# EPM1270.net
KiCad netlist of a schematic drawn in Altium Designer
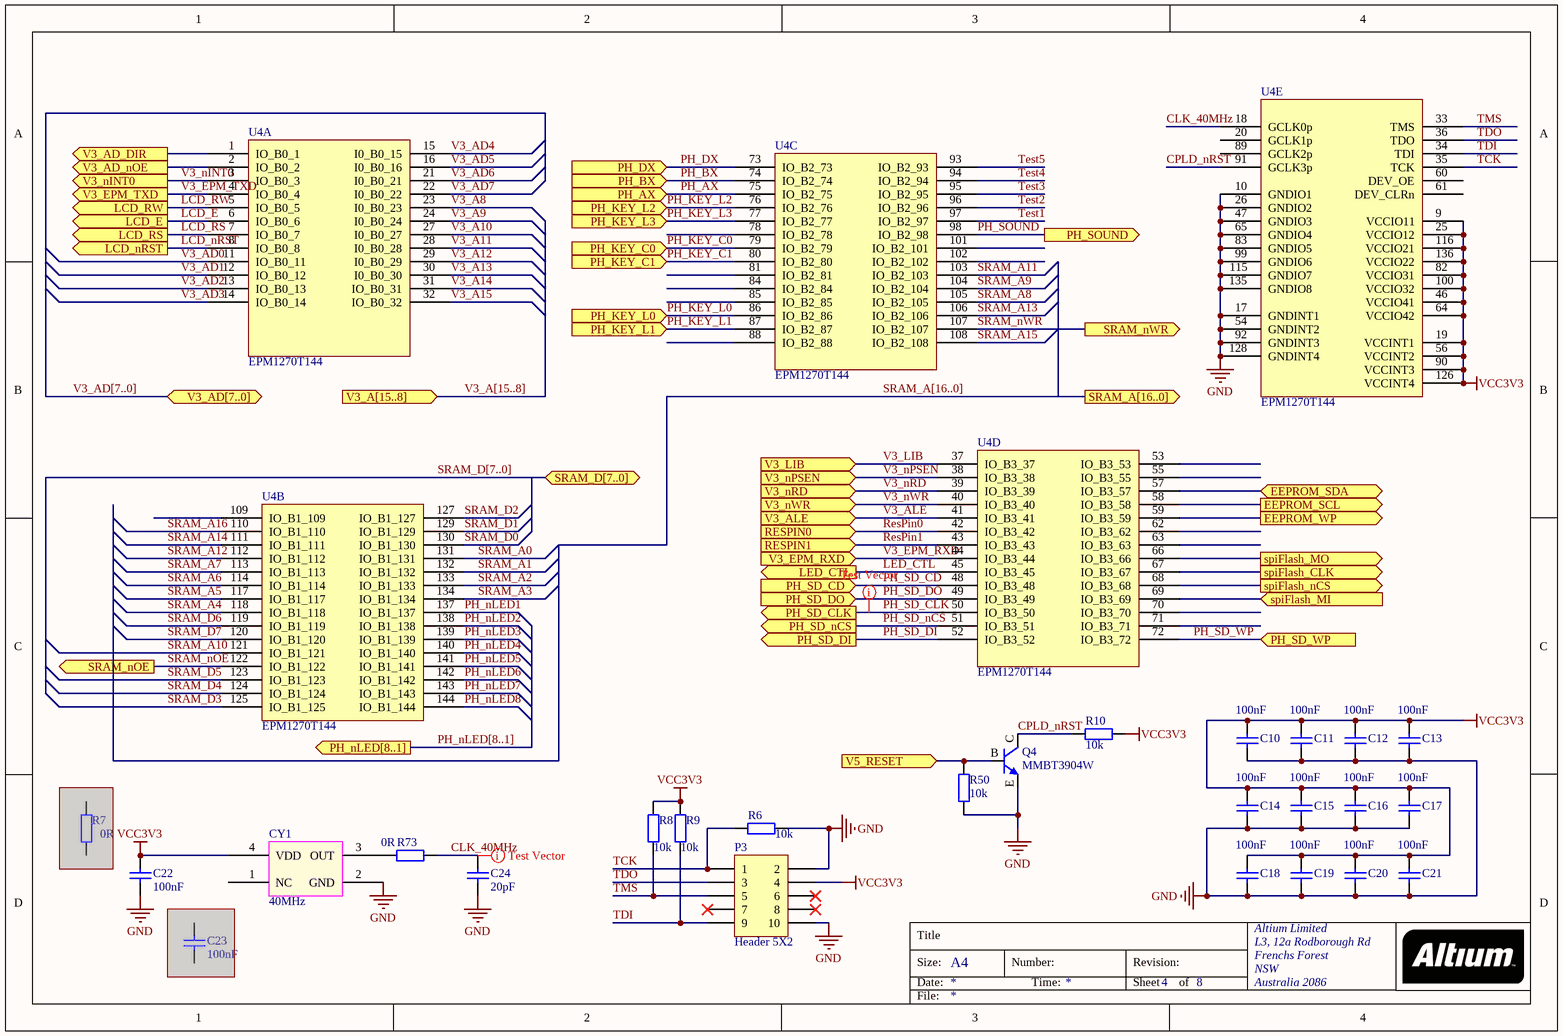
[diagram p0: EPM1270.SchDoc]

(export (version "E")
  (design (tool "Eeschema 10.0.6"))
  (components
    (comp (ref "C10") (value "100nF") (footprint "R0603") (libsource (lib "MyYX") (part "CAP_04")))
    (comp (ref "C11") (value "100nF") (footprint "R0603") (libsource (lib "MyYX") (part "CAP_04")))
    (comp (ref "C12") (value "100nF") (footprint "R0603") (libsource (lib "MyYX") (part "CAP_04")))
    (comp (ref "C13") (value "100nF") (footprint "R0603") (libsource (lib "MyYX") (part "CAP_04")))
    (comp (ref "C14") (value "100nF") (footprint "R0603") (libsource (lib "MyYX") (part "CAP_04")))
    (comp (ref "C15") (value "100nF") (footprint "R0603") (libsource (lib "MyYX") (part "CAP_04")))
    (comp (ref "C16") (value "100nF") (footprint "R0603") (libsource (lib "MyYX") (part "CAP_04")))
    (comp (ref "C17") (value "100nF") (footprint "R0603") (libsource (lib "MyYX") (part "CAP_04")))
    (comp (ref "C18") (value "100nF") (footprint "R0603") (libsource (lib "MyYX") (part "CAP_04")))
    (comp (ref "C19") (value "100nF") (footprint "R0603") (libsource (lib "MyYX") (part "CAP_04")))
    (comp (ref "C20") (value "100nF") (footprint "R0603") (libsource (lib "MyYX") (part "CAP_04")))
    (comp (ref "C21") (value "100nF") (footprint "R0603") (libsource (lib "MyYX") (part "CAP_04")))
    (comp (ref "C22") (value "100nF") (footprint "R0603") (libsource (lib "MyYX") (part "CAP_04")))
    (comp (ref "C23") (value "100nF") (footprint "R0603") (libsource (lib "MyYX") (part "CAP_04")))
    (comp (ref "C24")
      (value "20pF")
      (footprint "R0603")
      (fields (field (name "Comment") "100nF"))
      (libsource (lib "MyYX") (part "CAP_04"))
    )
    (comp (ref "CY1")
      (value "40MHz")
      (footprint "XCY4_5032")
      (description "Active crystal")
      (libsource (lib "MyYX") (part "XTAL_4P"))
    )
    (comp (ref "P3")
      (value "Header 5X2")
      (footprint "HDR2X5")
      (description "Header, 5-Pin, Dual row")
      (fields (field (name "PUBLISHER") "Altium Limited"))
      (libsource (lib "Miscellaneous Connectors") (part "Header 5X2"))
    )
    (comp (ref "Q4") (value "MMBT3904W") (footprint "SOT_23") (libsource (lib "MyYX") (part "MMBT3904TT1G")))
    (comp (ref "R6")
      (value "10k")
      (footprint "R0603")
      (description "0402")
      (libsource (lib "") (part "RES_04_1"))
    )
    (comp (ref "R7")
      (value "0R")
      (footprint "R0603")
      (description "0402")
      (libsource (lib "MyYX") (part "RES_04"))
    )
    (comp (ref "R8")
      (value "10k")
      (footprint "R0603")
      (description "0402")
      (libsource (lib "") (part "RES_04_2"))
    )
    (comp (ref "R9")
      (value "10k")
      (footprint "R0603")
      (description "0402")
      (libsource (lib "") (part "RES_04_2"))
    )
    (comp (ref "R10")
      (value "10k")
      (footprint "R0603")
      (description "0402")
      (libsource (lib "") (part "RES_04_3"))
    )
    (comp (ref "R50")
      (value "10k")
      (footprint "R0603")
      (description "0402")
      (libsource (lib "MyYX") (part "RES_04"))
    )
    (comp (ref "R73")
      (value "0R")
      (footprint "R0603")
      (description "0402")
      (libsource (lib "") (part "RES_04_3"))
    )
    (comp (ref "U4")
      (value "EPM1270T144")
      (footprint "EPM1270T144-TQFP")
      (libsource (lib "MyYX") (part "EPM1270T144"))
    )
  )
  (nets
    (net (code "1") (name "/CLK_40MHz") (class "Default")
      (node (ref "C24") (pin "1") (pinfunction "1_1") (pintype "passive"))
      (node (ref "R73") (pin "2") (pinfunction "2_2") (pintype "passive"))
      (node (ref "U4") (pin "18") (pinfunction "GCLK0p_18") (pintype "passive"))
    )
    (net (code "2") (name "/CPLD_nRST") (class "Default")
      (node (ref "Q4") (pin "C") (pinfunction "C_C") (pintype "passive"))
      (node (ref "R10") (pin "1") (pinfunction "1_1") (pintype "passive"))
      (node (ref "U4") (pin "91") (pinfunction "GCLK3p_91") (pintype "passive"))
    )
    (net (code "3") (name "/EEPROM_SCL") (class "Default")
      (node (ref "U4") (pin "58") (pinfunction "IO_B3_58_58") (pintype "passive"))
    )
    (net (code "4") (name "/EEPROM_SDA") (class "Default")
      (node (ref "U4") (pin "57") (pinfunction "IO_B3_57_57") (pintype "passive"))
    )
    (net (code "5") (name "/EEPROM_WP") (class "Default")
      (node (ref "U4") (pin "59") (pinfunction "IO_B3_59_59") (pintype "passive"))
    )
    (net (code "6") (name "/LCD_E") (class "Default")
      (node (ref "U4") (pin "6") (pinfunction "IO_B0_6_6") (pintype "passive"))
    )
    (net (code "7") (name "/LCD_RS") (class "Default")
      (node (ref "U4") (pin "7") (pinfunction "IO_B0_7_7") (pintype "passive"))
    )
    (net (code "8") (name "/LCD_RW") (class "Default")
      (node (ref "U4") (pin "5") (pinfunction "IO_B0_5_5") (pintype "passive"))
    )
    (net (code "9") (name "/LCD_nRST") (class "Default")
      (node (ref "U4") (pin "8") (pinfunction "IO_B0_8_8") (pintype "passive"))
    )
    (net (code "10") (name "/LED_CTL") (class "Default")
      (node (ref "U4") (pin "45") (pinfunction "IO_B3_45_45") (pintype "passive"))
    )
    (net (code "11") (name "/PH_AX") (class "Default")
      (node (ref "U4") (pin "75") (pinfunction "IO_B2_75_75") (pintype "passive"))
    )
    (net (code "12") (name "/PH_BX") (class "Default")
      (node (ref "U4") (pin "74") (pinfunction "IO_B2_74_74") (pintype "passive"))
    )
    (net (code "13") (name "/PH_DX") (class "Default")
      (node (ref "U4") (pin "73") (pinfunction "IO_B2_73_73") (pintype "passive"))
    )
    (net (code "14") (name "/PH_KEY_C0") (class "Default")
      (node (ref "U4") (pin "79") (pinfunction "IO_B2_79_79") (pintype "passive"))
    )
    (net (code "15") (name "/PH_KEY_C1") (class "Default")
      (node (ref "U4") (pin "80") (pinfunction "IO_B2_80_80") (pintype "passive"))
    )
    (net (code "16") (name "/PH_KEY_L0") (class "Default")
      (node (ref "U4") (pin "86") (pinfunction "IO_B2_86_86") (pintype "passive"))
    )
    (net (code "17") (name "/PH_KEY_L1") (class "Default")
      (node (ref "U4") (pin "87") (pinfunction "IO_B2_87_87") (pintype "passive"))
    )
    (net (code "18") (name "/PH_KEY_L2") (class "Default")
      (node (ref "U4") (pin "76") (pinfunction "IO_B2_76_76") (pintype "passive"))
    )
    (net (code "19") (name "/PH_KEY_L3") (class "Default")
      (node (ref "U4") (pin "77") (pinfunction "IO_B2_77_77") (pintype "passive"))
    )
    (net (code "20") (name "/PH_SD_CD") (class "Default")
      (node (ref "U4") (pin "48") (pinfunction "IO_B3_48_48") (pintype "passive"))
    )
    (net (code "21") (name "/PH_SD_CLK") (class "Default")
      (node (ref "U4") (pin "50") (pinfunction "IO_B3_50_50") (pintype "passive"))
    )
    (net (code "22") (name "/PH_SD_DI") (class "Default")
      (node (ref "U4") (pin "52") (pinfunction "IO_B3_52_52") (pintype "passive"))
    )
    (net (code "23") (name "/PH_SD_DO") (class "Default")
      (node (ref "U4") (pin "49") (pinfunction "IO_B3_49_49") (pintype "passive"))
    )
    (net (code "24") (name "/PH_SD_WP") (class "Default")
      (node (ref "U4") (pin "72") (pinfunction "IO_B3_72_72") (pintype "passive"))
    )
    (net (code "25") (name "/PH_SD_nCS") (class "Default")
      (node (ref "U4") (pin "51") (pinfunction "IO_B3_51_51") (pintype "passive"))
    )
    (net (code "26") (name "/PH_SOUND") (class "Default")
      (node (ref "U4") (pin "98") (pinfunction "IO_B2_98_98") (pintype "passive"))
    )
    (net (code "27") (name "/PH_nLED1") (class "Default")
      (node (ref "U4") (pin "137") (pinfunction "IO_B1_137_137") (pintype "passive"))
    )
    (net (code "28") (name "/PH_nLED2") (class "Default")
      (node (ref "U4") (pin "138") (pinfunction "IO_B1_138_138") (pintype "passive"))
    )
    (net (code "29") (name "/PH_nLED3") (class "Default")
      (node (ref "U4") (pin "139") (pinfunction "IO_B1_139_139") (pintype "passive"))
    )
    (net (code "30") (name "/PH_nLED4") (class "Default")
      (node (ref "U4") (pin "140") (pinfunction "IO_B1_140_140") (pintype "passive"))
    )
    (net (code "31") (name "/PH_nLED5") (class "Default")
      (node (ref "U4") (pin "141") (pinfunction "IO_B1_141_141") (pintype "passive"))
    )
    (net (code "32") (name "/PH_nLED6") (class "Default")
      (node (ref "U4") (pin "142") (pinfunction "IO_B1_142_142") (pintype "passive"))
    )
    (net (code "33") (name "/PH_nLED7") (class "Default")
      (node (ref "U4") (pin "143") (pinfunction "IO_B1_143_143") (pintype "passive"))
    )
    (net (code "34") (name "/PH_nLED8") (class "Default")
      (node (ref "U4") (pin "144") (pinfunction "IO_B1_144_144") (pintype "passive"))
    )
    (net (code "36") (name "/ResPin0") (class "Default")
      (node (ref "U4") (pin "42") (pinfunction "IO_B3_42_42") (pintype "passive"))
    )
    (net (code "37") (name "/ResPin1") (class "Default")
      (node (ref "U4") (pin "43") (pinfunction "IO_B3_43_43") (pintype "passive"))
    )
    (net (code "38") (name "/SRAM_A0") (class "Default")
      (node (ref "U4") (pin "131") (pinfunction "IO_B1_131_131") (pintype "passive"))
    )
    (net (code "39") (name "/SRAM_A1") (class "Default")
      (node (ref "U4") (pin "132") (pinfunction "IO_B1_132_132") (pintype "passive"))
    )
    (net (code "40") (name "/SRAM_A2") (class "Default")
      (node (ref "U4") (pin "133") (pinfunction "IO_B1_133_133") (pintype "passive"))
    )
    (net (code "41") (name "/SRAM_A3") (class "Default")
      (node (ref "U4") (pin "134") (pinfunction "IO_B1_134_134") (pintype "passive"))
    )
    (net (code "42") (name "/SRAM_A4") (class "Default")
      (node (ref "U4") (pin "118") (pinfunction "IO_B1_118_118") (pintype "passive"))
    )
    (net (code "43") (name "/SRAM_A5") (class "Default")
      (node (ref "U4") (pin "117") (pinfunction "IO_B1_117_117") (pintype "passive"))
    )
    (net (code "44") (name "/SRAM_A6") (class "Default")
      (node (ref "U4") (pin "114") (pinfunction "IO_B1_114_114") (pintype "passive"))
    )
    (net (code "45") (name "/SRAM_A7") (class "Default")
      (node (ref "U4") (pin "113") (pinfunction "IO_B1_113_113") (pintype "passive"))
    )
    (net (code "46") (name "/SRAM_A8") (class "Default")
      (node (ref "U4") (pin "105") (pinfunction "IO_B2_105_105") (pintype "passive"))
    )
    (net (code "47") (name "/SRAM_A9") (class "Default")
      (node (ref "U4") (pin "104") (pinfunction "IO_B2_104_104") (pintype "passive"))
    )
    (net (code "48") (name "/SRAM_A10") (class "Default")
      (node (ref "U4") (pin "121") (pinfunction "IO_B1_121_121") (pintype "passive"))
    )
    (net (code "49") (name "/SRAM_A11") (class "Default")
      (node (ref "U4") (pin "103") (pinfunction "IO_B2_103_103") (pintype "passive"))
    )
    (net (code "50") (name "/SRAM_A12") (class "Default")
      (node (ref "U4") (pin "112") (pinfunction "IO_B1_112_112") (pintype "passive"))
    )
    (net (code "51") (name "/SRAM_A13") (class "Default")
      (node (ref "U4") (pin "106") (pinfunction "IO_B2_106_106") (pintype "passive"))
    )
    (net (code "52") (name "/SRAM_A14") (class "Default")
      (node (ref "U4") (pin "111") (pinfunction "IO_B1_111_111") (pintype "passive"))
    )
    (net (code "53") (name "/SRAM_A15") (class "Default")
      (node (ref "U4") (pin "108") (pinfunction "IO_B2_108_108") (pintype "passive"))
    )
    (net (code "54") (name "/SRAM_A16") (class "Default")
      (node (ref "U4") (pin "110") (pinfunction "IO_B1_110_110") (pintype "passive"))
    )
    (net (code "56") (name "/SRAM_D0") (class "Default")
      (node (ref "U4") (pin "130") (pinfunction "IO_B1_130_130") (pintype "passive"))
    )
    (net (code "57") (name "/SRAM_D1") (class "Default")
      (node (ref "U4") (pin "129") (pinfunction "IO_B1_129_129") (pintype "passive"))
    )
    (net (code "58") (name "/SRAM_D2") (class "Default")
      (node (ref "U4") (pin "127") (pinfunction "IO_B1_127_127") (pintype "passive"))
    )
    (net (code "59") (name "/SRAM_D3") (class "Default")
      (node (ref "U4") (pin "125") (pinfunction "IO_B1_125_125") (pintype "passive"))
    )
    (net (code "60") (name "/SRAM_D4") (class "Default")
      (node (ref "U4") (pin "124") (pinfunction "IO_B1_124_124") (pintype "passive"))
    )
    (net (code "61") (name "/SRAM_D5") (class "Default")
      (node (ref "U4") (pin "123") (pinfunction "IO_B1_123_123") (pintype "passive"))
    )
    (net (code "62") (name "/SRAM_D6") (class "Default")
      (node (ref "U4") (pin "119") (pinfunction "IO_B1_119_119") (pintype "passive"))
    )
    (net (code "63") (name "/SRAM_D7") (class "Default")
      (node (ref "U4") (pin "120") (pinfunction "IO_B1_120_120") (pintype "passive"))
    )
    (net (code "65") (name "/SRAM_nOE") (class "Default")
      (node (ref "U4") (pin "122") (pinfunction "IO_B1_122_122") (pintype "passive"))
    )
    (net (code "66") (name "/SRAM_nWR") (class "Default")
      (node (ref "U4") (pin "107") (pinfunction "IO_B2_107_107") (pintype "passive"))
    )
    (net (code "67") (name "/TCK") (class "Default")
      (node (ref "P3") (pin "1") (pinfunction "1_1") (pintype "passive"))
      (node (ref "R6") (pin "2") (pinfunction "2_2") (pintype "passive"))
      (node (ref "U4") (pin "35") (pinfunction "TCK_35") (pintype "passive"))
    )
    (net (code "68") (name "/TDI") (class "Default")
      (node (ref "P3") (pin "9") (pinfunction "9_9") (pintype "passive"))
      (node (ref "R9") (pin "1") (pinfunction "1_1") (pintype "passive"))
      (node (ref "U4") (pin "34") (pinfunction "TDI_34") (pintype "passive"))
    )
    (net (code "69") (name "/TDO") (class "Default")
      (node (ref "P3") (pin "3") (pinfunction "3_3") (pintype "passive"))
      (node (ref "U4") (pin "36") (pinfunction "TDO_36") (pintype "passive"))
    )
    (net (code "70") (name "/TMS") (class "Default")
      (node (ref "P3") (pin "5") (pinfunction "5_5") (pintype "passive"))
      (node (ref "R8") (pin "1") (pinfunction "1_1") (pintype "passive"))
      (node (ref "U4") (pin "33") (pinfunction "TMS_33") (pintype "passive"))
    )
    (net (code "71") (name "/Test1") (class "Default")
      (node (ref "U4") (pin "97") (pinfunction "IO_B2_97_97") (pintype "passive"))
    )
    (net (code "72") (name "/Test2") (class "Default")
      (node (ref "U4") (pin "96") (pinfunction "IO_B2_96_96") (pintype "passive"))
    )
    (net (code "73") (name "/Test3") (class "Default")
      (node (ref "U4") (pin "95") (pinfunction "IO_B2_95_95") (pintype "passive"))
    )
    (net (code "74") (name "/Test4") (class "Default")
      (node (ref "U4") (pin "94") (pinfunction "IO_B2_94_94") (pintype "passive"))
    )
    (net (code "75") (name "/Test5") (class "Default")
      (node (ref "U4") (pin "93") (pinfunction "IO_B2_93_93") (pintype "passive"))
    )
    (net (code "76") (name "/V3_A8") (class "Default")
      (node (ref "U4") (pin "23") (pinfunction "I0_B0_23_23") (pintype "passive"))
    )
    (net (code "77") (name "/V3_A9") (class "Default")
      (node (ref "U4") (pin "24") (pinfunction "I0_B0_24_24") (pintype "passive"))
    )
    (net (code "78") (name "/V3_A10") (class "Default")
      (node (ref "U4") (pin "27") (pinfunction "I0_B0_27_27") (pintype "passive"))
    )
    (net (code "79") (name "/V3_A11") (class "Default")
      (node (ref "U4") (pin "28") (pinfunction "I0_B0_28_28") (pintype "passive"))
    )
    (net (code "80") (name "/V3_A12") (class "Default")
      (node (ref "U4") (pin "29") (pinfunction "I0_B0_29_29") (pintype "passive"))
    )
    (net (code "81") (name "/V3_A13") (class "Default")
      (node (ref "U4") (pin "30") (pinfunction "I0_B0_30_30") (pintype "passive"))
    )
    (net (code "82") (name "/V3_A14") (class "Default")
      (node (ref "U4") (pin "31") (pinfunction "IO_B0_31_31") (pintype "passive"))
    )
    (net (code "83") (name "/V3_A15") (class "Default")
      (node (ref "U4") (pin "32") (pinfunction "IO_B0_32_32") (pintype "passive"))
    )
    (net (code "84") (name "/V3_AD0") (class "Default")
      (node (ref "U4") (pin "11") (pinfunction "IO_B0_11_11") (pintype "passive"))
    )
    (net (code "85") (name "/V3_AD1") (class "Default")
      (node (ref "U4") (pin "12") (pinfunction "IO_B0_12_12") (pintype "passive"))
    )
    (net (code "86") (name "/V3_AD2") (class "Default")
      (node (ref "U4") (pin "13") (pinfunction "IO_B0_13_13") (pintype "passive"))
    )
    (net (code "87") (name "/V3_AD3") (class "Default")
      (node (ref "U4") (pin "14") (pinfunction "IO_B0_14_14") (pintype "passive"))
    )
    (net (code "88") (name "/V3_AD4") (class "Default")
      (node (ref "U4") (pin "15") (pinfunction "I0_B0_15_15") (pintype "passive"))
    )
    (net (code "89") (name "/V3_AD5") (class "Default")
      (node (ref "U4") (pin "16") (pinfunction "I0_B0_16_16") (pintype "passive"))
    )
    (net (code "90") (name "/V3_AD6") (class "Default")
      (node (ref "U4") (pin "21") (pinfunction "I0_B0_21_21") (pintype "passive"))
    )
    (net (code "91") (name "/V3_AD7") (class "Default")
      (node (ref "U4") (pin "22") (pinfunction "I0_B0_22_22") (pintype "passive"))
    )
    (net (code "93") (name "/V3_AD_DIR") (class "Default")
      (node (ref "U4") (pin "1") (pinfunction "IO_B0_1_1") (pintype "passive"))
    )
    (net (code "94") (name "/V3_AD_nOE") (class "Default")
      (node (ref "U4") (pin "2") (pinfunction "IO_B0_2_2") (pintype "passive"))
    )
    (net (code "95") (name "/V3_ALE") (class "Default")
      (node (ref "U4") (pin "41") (pinfunction "IO_B3_41_41") (pintype "passive"))
    )
    (net (code "97") (name "/V3_EPM_RXD") (class "Default")
      (node (ref "U4") (pin "44") (pinfunction "IO_B3_44_44") (pintype "passive"))
    )
    (net (code "98") (name "/V3_EPM_TXD") (class "Default")
      (node (ref "U4") (pin "4") (pinfunction "IO_B0_4_4") (pintype "passive"))
    )
    (net (code "99") (name "/V3_LIB") (class "Default")
      (node (ref "U4") (pin "37") (pinfunction "IO_B3_37_37") (pintype "passive"))
    )
    (net (code "100") (name "/V3_nINT0") (class "Default")
      (node (ref "U4") (pin "3") (pinfunction "IO_B0_3_3") (pintype "passive"))
    )
    (net (code "101") (name "/V3_nPSEN") (class "Default")
      (node (ref "U4") (pin "38") (pinfunction "IO_B3_38_38") (pintype "passive"))
    )
    (net (code "102") (name "/V3_nRD") (class "Default")
      (node (ref "U4") (pin "39") (pinfunction "IO_B3_39_39") (pintype "passive"))
    )
    (net (code "103") (name "/V3_nWR") (class "Default")
      (node (ref "U4") (pin "40") (pinfunction "IO_B3_40_40") (pintype "passive"))
    )
    (net (code "104") (name "/V5_RESET") (class "Default")
      (node (ref "Q4") (pin "B") (pinfunction "B_B") (pintype "passive"))
      (node (ref "R50") (pin "1") (pinfunction "1_1") (pintype "passive"))
    )
    (net (code "105") (name "/spiFlash_CLK") (class "Default")
      (node (ref "U4") (pin "67") (pinfunction "IO_B3_67_67") (pintype "passive"))
    )
    (net (code "106") (name "/spiFlash_MI") (class "Default")
      (node (ref "U4") (pin "69") (pinfunction "IO_B3_69_69") (pintype "passive"))
    )
    (net (code "107") (name "/spiFlash_MO") (class "Default")
      (node (ref "U4") (pin "66") (pinfunction "IO_B3_66_66") (pintype "passive"))
    )
    (net (code "108") (name "/spiFlash_nCS") (class "Default")
      (node (ref "U4") (pin "68") (pinfunction "IO_B3_68_68") (pintype "passive"))
    )
    (net (code "109") (name "GND") (class "Default")
      (node (ref "C10") (pin "2") (pinfunction "2_2") (pintype "passive"))
      (node (ref "C11") (pin "2") (pinfunction "2_2") (pintype "passive"))
      (node (ref "C12") (pin "2") (pinfunction "2_2") (pintype "passive"))
      (node (ref "C13") (pin "2") (pinfunction "2_2") (pintype "passive"))
      (node (ref "C14") (pin "2") (pinfunction "2_2") (pintype "passive"))
      (node (ref "C15") (pin "2") (pinfunction "2_2") (pintype "passive"))
      (node (ref "C16") (pin "2") (pinfunction "2_2") (pintype "passive"))
      (node (ref "C17") (pin "2") (pinfunction "2_2") (pintype "passive"))
      (node (ref "C18") (pin "2") (pinfunction "2_2") (pintype "passive"))
      (node (ref "C19") (pin "2") (pinfunction "2_2") (pintype "passive"))
      (node (ref "C20") (pin "2") (pinfunction "2_2") (pintype "passive"))
      (node (ref "C21") (pin "2") (pinfunction "2_2") (pintype "passive"))
      (node (ref "C22") (pin "2") (pinfunction "2_2") (pintype "passive"))
      (node (ref "C24") (pin "2") (pinfunction "2_2") (pintype "passive"))
      (node (ref "CY1") (pin "2") (pinfunction "GND_2") (pintype "passive"))
      (node (ref "P3") (pin "10") (pinfunction "10_10") (pintype "passive"))
      (node (ref "P3") (pin "2") (pinfunction "2_2") (pintype "passive"))
      (node (ref "Q4") (pin "E") (pinfunction "E_E") (pintype "passive"))
      (node (ref "R50") (pin "2") (pinfunction "2_2") (pintype "passive"))
      (node (ref "R6") (pin "1") (pinfunction "1_1") (pintype "passive"))
      (node (ref "U4") (pin "10") (pinfunction "GNDIO1_10") (pintype "passive"))
      (node (ref "U4") (pin "115") (pinfunction "GNDIO7_115") (pintype "passive"))
      (node (ref "U4") (pin "128") (pinfunction "GNDINT4_128") (pintype "passive"))
      (node (ref "U4") (pin "135") (pinfunction "GNDIO8_135") (pintype "passive"))
      (node (ref "U4") (pin "17") (pinfunction "GNDINT1_17") (pintype "passive"))
      (node (ref "U4") (pin "26") (pinfunction "GNDIO2_26") (pintype "passive"))
      (node (ref "U4") (pin "47") (pinfunction "GNDIO3_47") (pintype "passive"))
      (node (ref "U4") (pin "54") (pinfunction "GNDINT2_54") (pintype "passive"))
      (node (ref "U4") (pin "65") (pinfunction "GNDIO4_65") (pintype "passive"))
      (node (ref "U4") (pin "83") (pinfunction "GNDIO5_83") (pintype "passive"))
      (node (ref "U4") (pin "92") (pinfunction "GNDINT3_92") (pintype "passive"))
      (node (ref "U4") (pin "99") (pinfunction "GNDIO6_99") (pintype "passive"))
    )
    (net (code "110") (name "Net-(CY1-OUT)") (class "Default")
      (node (ref "CY1") (pin "3") (pinfunction "OUT_3") (pintype "passive"))
      (node (ref "R73") (pin "1") (pinfunction "1_1") (pintype "passive"))
    )
    (net (code "111") (name "VCC3V3") (class "Default")
      (node (ref "C10") (pin "1") (pinfunction "1_1") (pintype "passive"))
      (node (ref "C11") (pin "1") (pinfunction "1_1") (pintype "passive"))
      (node (ref "C12") (pin "1") (pinfunction "1_1") (pintype "passive"))
      (node (ref "C13") (pin "1") (pinfunction "1_1") (pintype "passive"))
      (node (ref "C14") (pin "1") (pinfunction "1_1") (pintype "passive"))
      (node (ref "C15") (pin "1") (pinfunction "1_1") (pintype "passive"))
      (node (ref "C16") (pin "1") (pinfunction "1_1") (pintype "passive"))
      (node (ref "C17") (pin "1") (pinfunction "1_1") (pintype "passive"))
      (node (ref "C18") (pin "1") (pinfunction "1_1") (pintype "passive"))
      (node (ref "C19") (pin "1") (pinfunction "1_1") (pintype "passive"))
      (node (ref "C20") (pin "1") (pinfunction "1_1") (pintype "passive"))
      (node (ref "C21") (pin "1") (pinfunction "1_1") (pintype "passive"))
      (node (ref "C22") (pin "1") (pinfunction "1_1") (pintype "passive"))
      (node (ref "CY1") (pin "4") (pinfunction "VDD_4") (pintype "passive"))
      (node (ref "P3") (pin "4") (pinfunction "4_4") (pintype "passive"))
      (node (ref "R10") (pin "2") (pinfunction "2_2") (pintype "passive"))
      (node (ref "R8") (pin "2") (pinfunction "2_2") (pintype "passive"))
      (node (ref "R9") (pin "2") (pinfunction "2_2") (pintype "passive"))
      (node (ref "U4") (pin "100") (pinfunction "VCCIO32_100") (pintype "passive"))
      (node (ref "U4") (pin "116") (pinfunction "VCCIO21_116") (pintype "passive"))
      (node (ref "U4") (pin "126") (pinfunction "VCCINT4_126") (pintype "passive"))
      (node (ref "U4") (pin "136") (pinfunction "VCCIO22_136") (pintype "passive"))
      (node (ref "U4") (pin "19") (pinfunction "VCCINT1_19") (pintype "passive"))
      (node (ref "U4") (pin "25") (pinfunction "VCCIO12_25") (pintype "passive"))
      (node (ref "U4") (pin "46") (pinfunction "VCCIO41_46") (pintype "passive"))
      (node (ref "U4") (pin "56") (pinfunction "VCCINT2_56") (pintype "passive"))
      (node (ref "U4") (pin "64") (pinfunction "VCCIO42_64") (pintype "passive"))
      (node (ref "U4") (pin "82") (pinfunction "VCCIO31_82") (pintype "passive"))
      (node (ref "U4") (pin "9") (pinfunction "VCCIO11_9") (pintype "passive"))
      (node (ref "U4") (pin "90") (pinfunction "VCCINT3_90") (pintype "passive"))
    )
    (net (code "112") (name "unconnected-(C23-Pad1)") (class "Default")
      (node (ref "C23") (pin "1") (pinfunction "1_1") (pintype "passive"))
    )
    (net (code "113") (name "unconnected-(C23-Pad2)") (class "Default")
      (node (ref "C23") (pin "2") (pinfunction "2_2") (pintype "passive"))
    )
    (net (code "114") (name "unconnected-(CY1-NC-Pad1)") (class "Default")
      (node (ref "CY1") (pin "1") (pinfunction "NC_1") (pintype "passive"))
    )
    (net (code "115") (name "unconnected-(P3-Pad6)") (class "Default")
      (node (ref "P3") (pin "6") (pinfunction "6_6") (pintype "passive+no_connect"))
    )
    (net (code "116") (name "unconnected-(P3-Pad7)") (class "Default")
      (node (ref "P3") (pin "7") (pinfunction "7_7") (pintype "passive+no_connect"))
    )
    (net (code "117") (name "unconnected-(P3-Pad8)") (class "Default")
      (node (ref "P3") (pin "8") (pinfunction "8_8") (pintype "passive+no_connect"))
    )
    (net (code "118") (name "unconnected-(R7-Pad1)") (class "Default")
      (node (ref "R7") (pin "1") (pinfunction "1_1") (pintype "passive"))
    )
    (net (code "119") (name "unconnected-(R7-Pad2)") (class "Default")
      (node (ref "R7") (pin "2") (pinfunction "2_2") (pintype "passive"))
    )
    (net (code "120") (name "unconnected-(U4B-IO_B1_109-Pad109)") (class "Default")
      (node (ref "U4") (pin "109") (pinfunction "IO_B1_109_109") (pintype "passive"))
    )
    (net (code "121") (name "unconnected-(U4C-IO_B2_78-Pad78)") (class "Default")
      (node (ref "U4") (pin "78") (pinfunction "IO_B2_78_78") (pintype "passive"))
    )
    (net (code "122") (name "unconnected-(U4C-IO_B2_81-Pad81)") (class "Default")
      (node (ref "U4") (pin "81") (pinfunction "IO_B2_81_81") (pintype "passive"))
    )
    (net (code "123") (name "unconnected-(U4C-IO_B2_84-Pad84)") (class "Default")
      (node (ref "U4") (pin "84") (pinfunction "IO_B2_84_84") (pintype "passive"))
    )
    (net (code "124") (name "unconnected-(U4C-IO_B2_85-Pad85)") (class "Default")
      (node (ref "U4") (pin "85") (pinfunction "IO_B2_85_85") (pintype "passive"))
    )
    (net (code "125") (name "unconnected-(U4C-IO_B2_88-Pad88)") (class "Default")
      (node (ref "U4") (pin "88") (pinfunction "IO_B2_88_88") (pintype "passive"))
    )
    (net (code "126") (name "unconnected-(U4C-IO_B2_101-Pad101)") (class "Default")
      (node (ref "U4") (pin "101") (pinfunction "IO_B2_101_101") (pintype "passive"))
    )
    (net (code "127") (name "unconnected-(U4C-IO_B2_102-Pad102)") (class "Default")
      (node (ref "U4") (pin "102") (pinfunction "IO_B2_102_102") (pintype "passive"))
    )
    (net (code "128") (name "unconnected-(U4D-IO_B3_53-Pad53)") (class "Default")
      (node (ref "U4") (pin "53") (pinfunction "IO_B3_53_53") (pintype "passive"))
    )
    (net (code "129") (name "unconnected-(U4D-IO_B3_55-Pad55)") (class "Default")
      (node (ref "U4") (pin "55") (pinfunction "IO_B3_55_55") (pintype "passive"))
    )
    (net (code "130") (name "unconnected-(U4D-IO_B3_62-Pad62)") (class "Default")
      (node (ref "U4") (pin "62") (pinfunction "IO_B3_62_62") (pintype "passive"))
    )
    (net (code "131") (name "unconnected-(U4D-IO_B3_63-Pad63)") (class "Default")
      (node (ref "U4") (pin "63") (pinfunction "IO_B3_63_63") (pintype "passive"))
    )
    (net (code "132") (name "unconnected-(U4D-IO_B3_70-Pad70)") (class "Default")
      (node (ref "U4") (pin "70") (pinfunction "IO_B3_70_70") (pintype "passive"))
    )
    (net (code "133") (name "unconnected-(U4D-IO_B3_71-Pad71)") (class "Default")
      (node (ref "U4") (pin "71") (pinfunction "IO_B3_71_71") (pintype "passive"))
    )
    (net (code "134") (name "unconnected-(U4E-DEV_CLRn-Pad61)") (class "Default")
      (node (ref "U4") (pin "61") (pinfunction "DEV_CLRn_61") (pintype "passive"))
    )
    (net (code "135") (name "unconnected-(U4E-DEV_OE-Pad60)") (class "Default")
      (node (ref "U4") (pin "60") (pinfunction "DEV_OE_60") (pintype "passive"))
    )
    (net (code "136") (name "unconnected-(U4E-GCLK1p-Pad20)") (class "Default")
      (node (ref "U4") (pin "20") (pinfunction "GCLK1p_20") (pintype "passive"))
    )
    (net (code "137") (name "unconnected-(U4E-GCLK2p-Pad89)") (class "Default")
      (node (ref "U4") (pin "89") (pinfunction "GCLK2p_89") (pintype "passive"))
    )
  )
)
